# clock_datapath.net
KiCad netlist of a schematic drawn in EAGLE
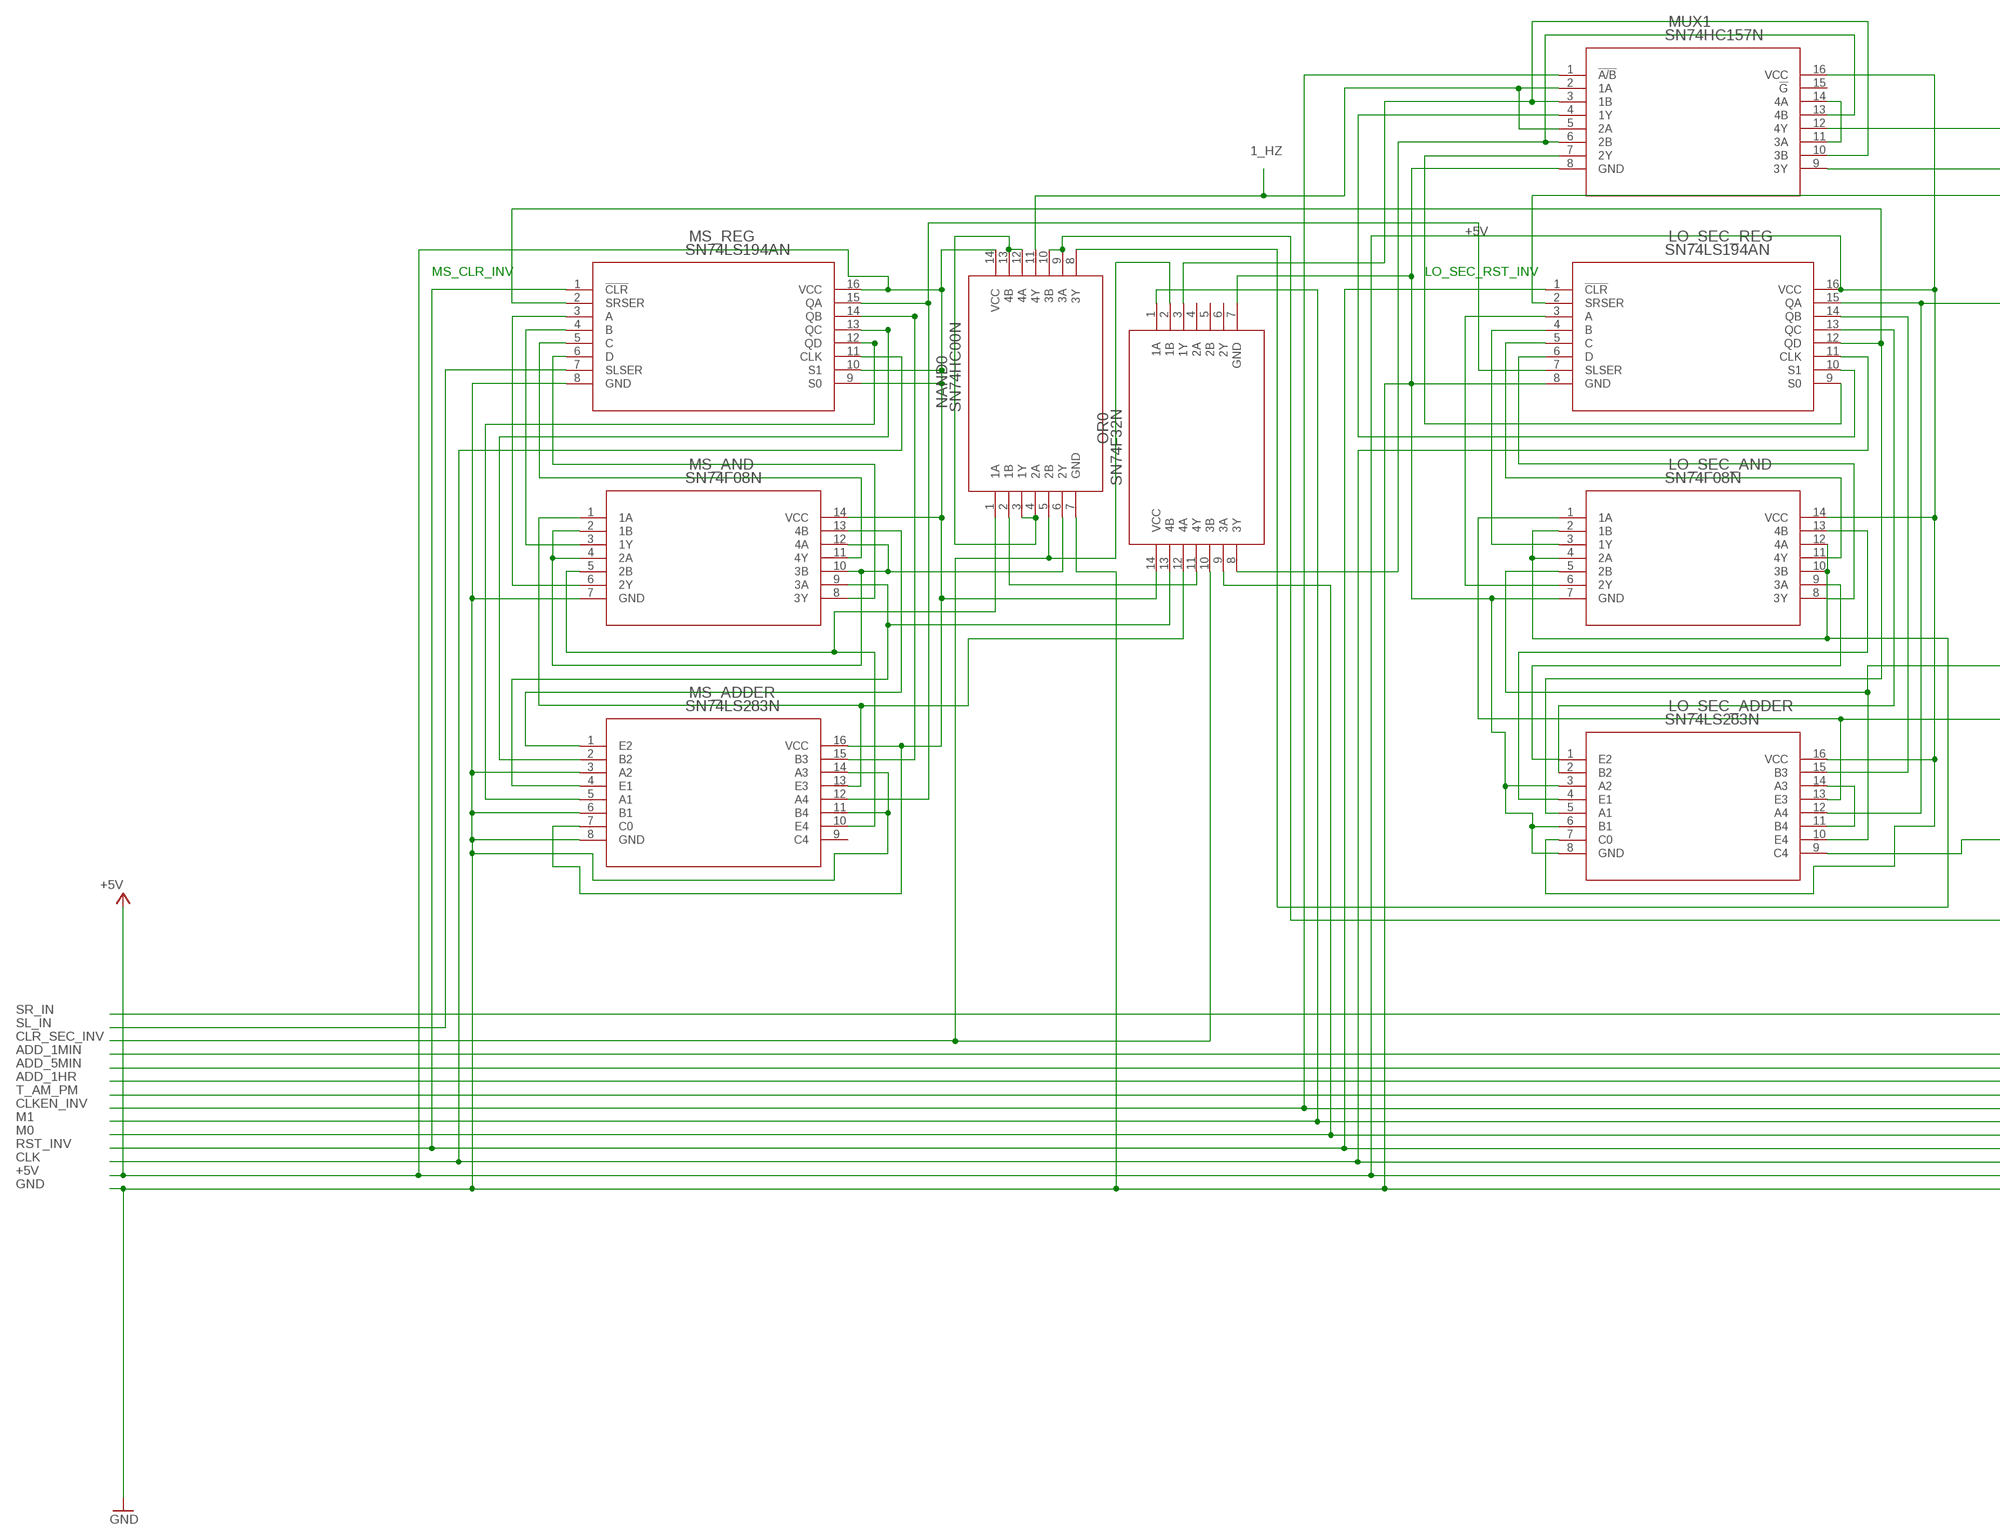
[diagram p0: schematic, sheet 1, part 1 of 3]
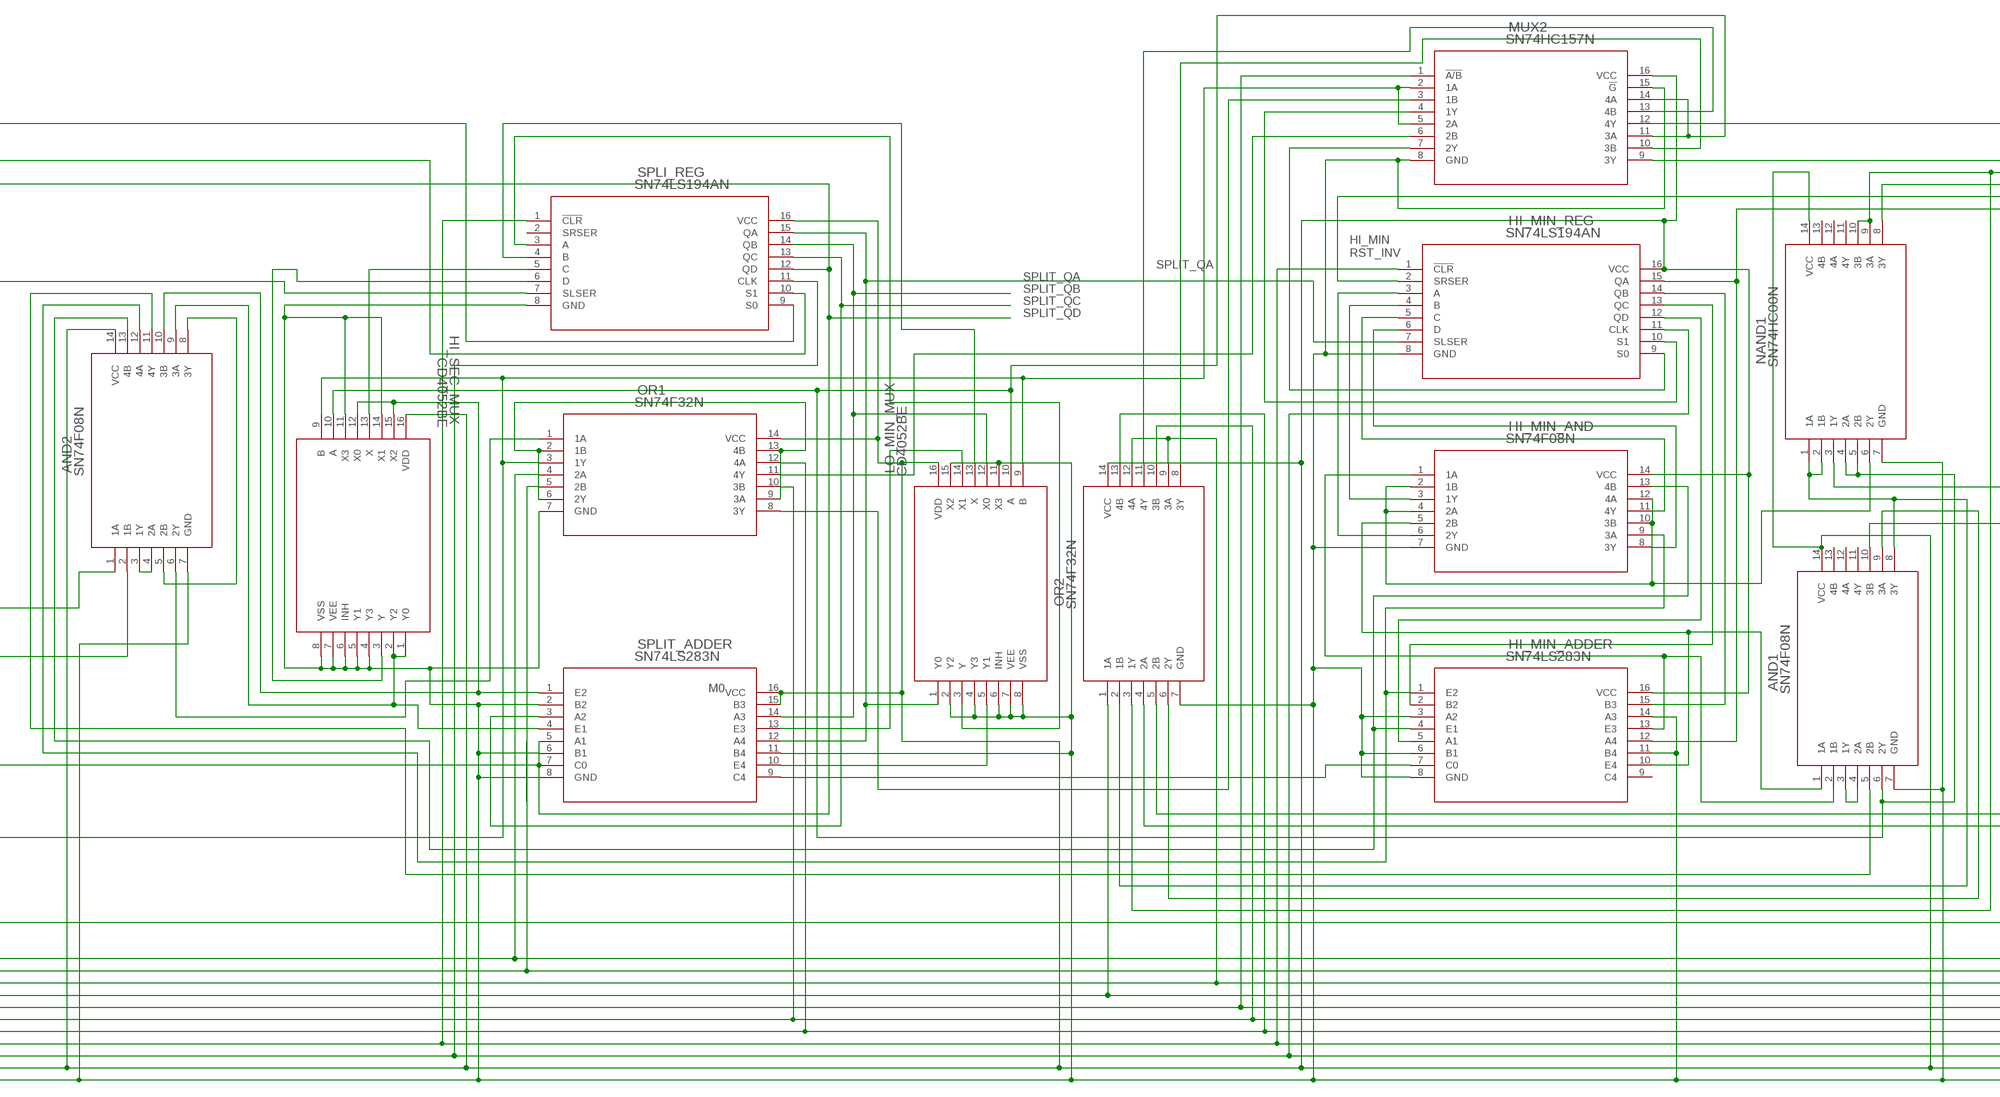
[diagram p1: schematic, sheet 1, part 2 of 3]
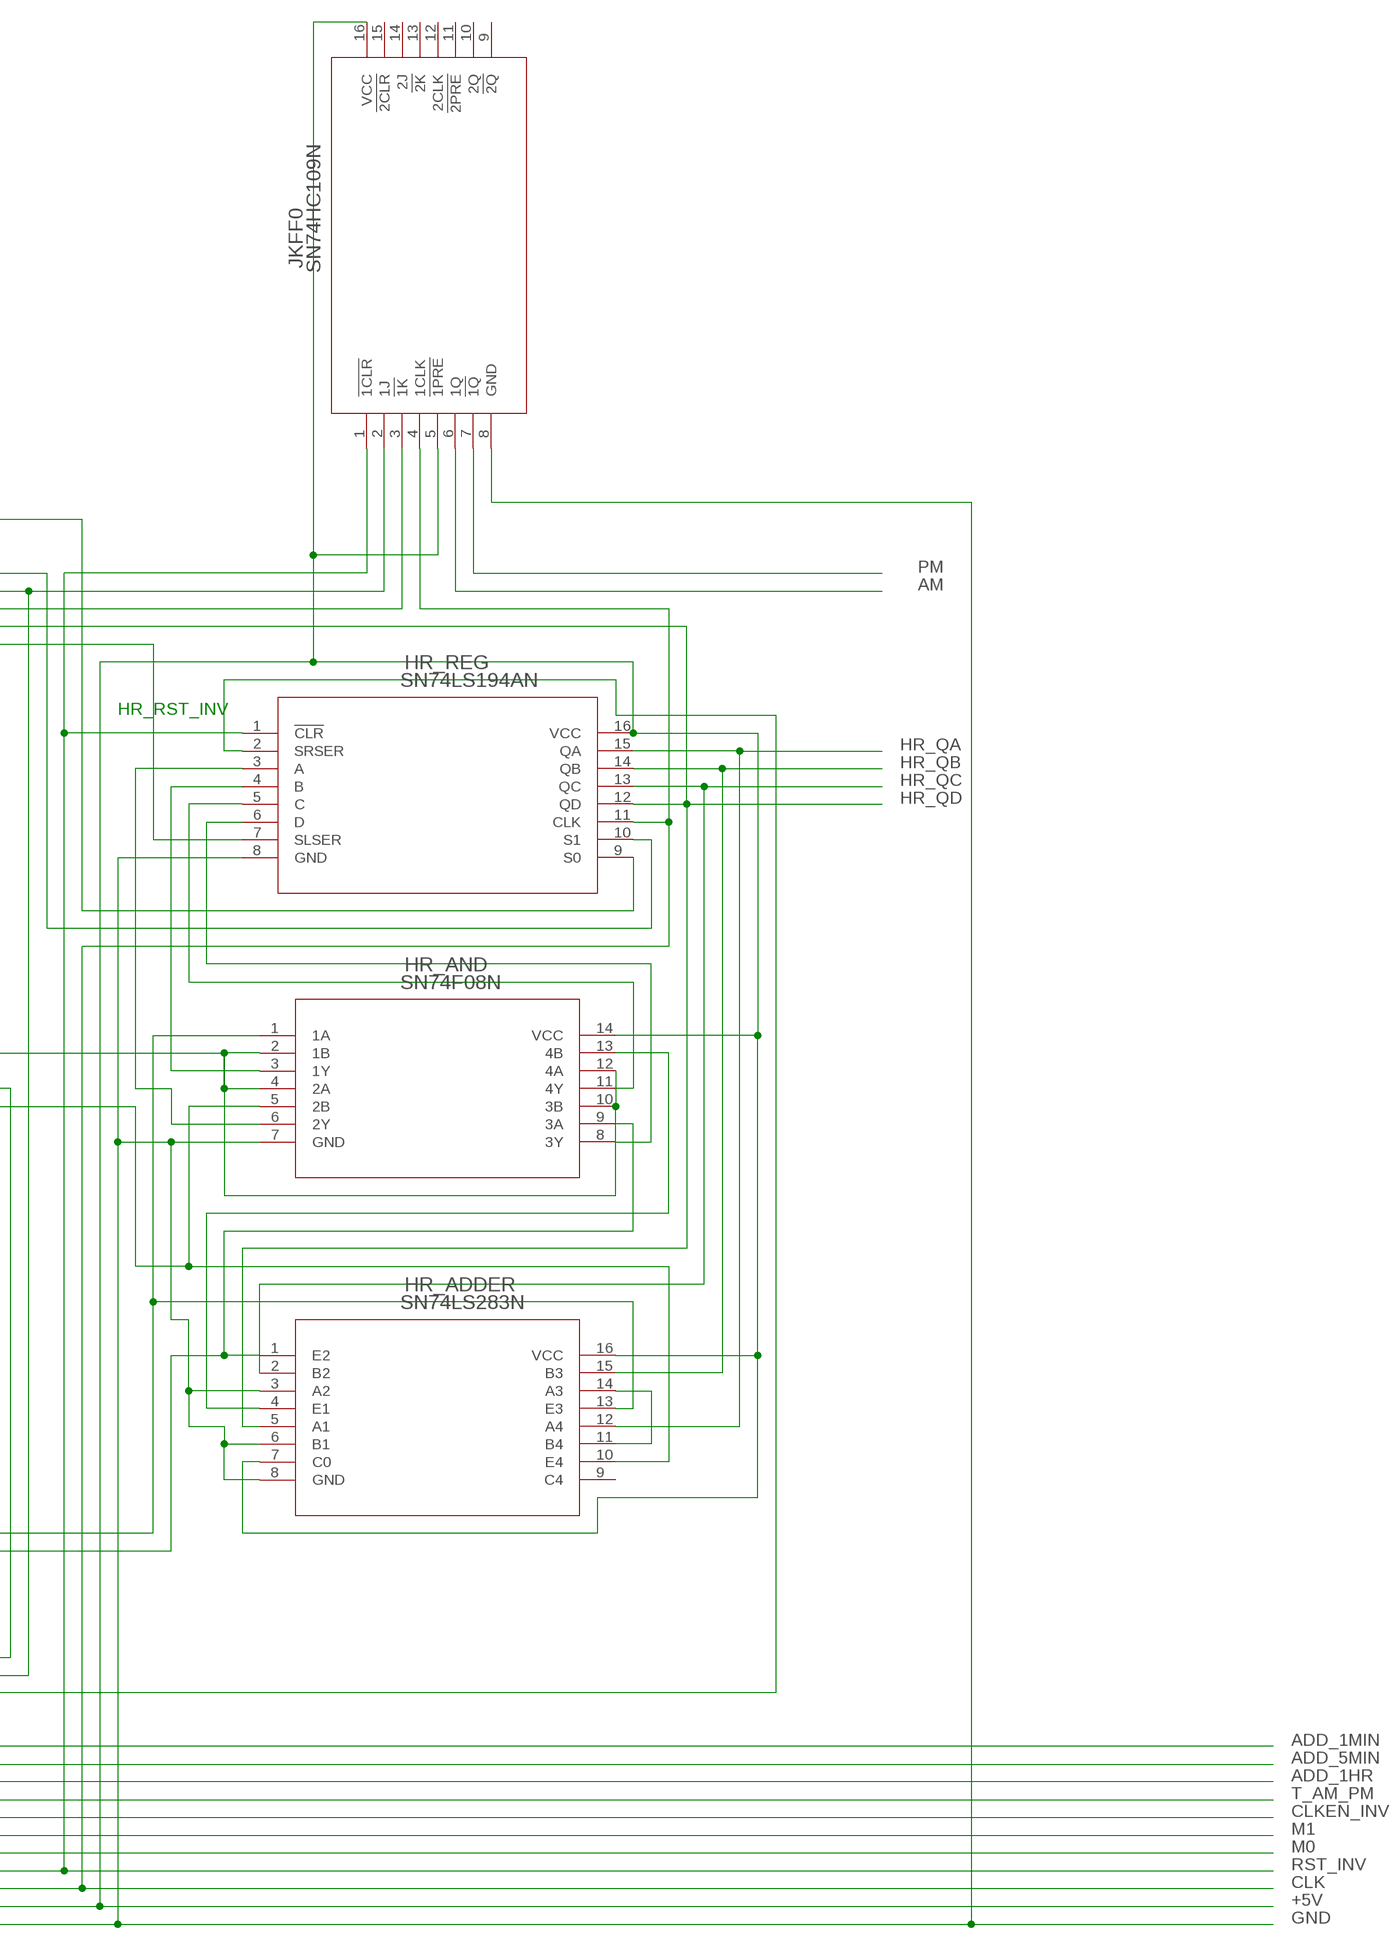
[diagram p2: schematic, sheet 1, part 3 of 3]

(export (version "E")
  (design (tool "Eeschema 10.0.6"))
  (components
    (comp (ref "AND1")
      (value "SN74F08N")
      (footprint "eagle-import:N14")
      (fields
        (field (name "GENERIC_PART_NUMBER") "SN74F08")
        (field (name "MANUFACTURER") "Texas Instruments")
      )
      (libsource (lib "eagle-import") (part "SN74F08N"))
    )
    (comp (ref "AND2")
      (value "SN74F08N")
      (footprint "eagle-import:N14")
      (fields
        (field (name "GENERIC_PART_NUMBER") "SN74F08")
        (field (name "MANUFACTURER") "Texas Instruments")
      )
      (libsource (lib "eagle-import") (part "SN74F08N"))
    )
    (comp (ref "HI_MIN_ADDER")
      (value "SN74LS283N")
      (footprint "eagle-import:N16")
      (fields
        (field (name "GENERIC_PART_NUMBER") "SN74LS283")
        (field (name "MANUFACTURER") "Texas Instruments")
      )
      (libsource (lib "eagle-import") (part "SN74LS283N"))
    )
    (comp (ref "HI_MIN_AND")
      (value "SN74F08N")
      (footprint "eagle-import:N14")
      (fields
        (field (name "GENERIC_PART_NUMBER") "SN74F08")
        (field (name "MANUFACTURER") "Texas Instruments")
      )
      (libsource (lib "eagle-import") (part "SN74F08N"))
    )
    (comp (ref "HI_MIN_REG")
      (value "SN74LS194AN")
      (footprint "eagle-import:N16")
      (fields
        (field (name "GENERIC_PART_NUMBER") "SN74LS194A")
        (field (name "MANUFACTURER") "Texas Instruments")
      )
      (libsource (lib "eagle-import") (part "SN74LS194AN"))
    )
    (comp (ref "HI_SEC_MUX")
      (value "CD4052BE")
      (footprint "eagle-import:N16")
      (fields
        (field (name "GENERIC_PART_NUMBER") "CD4052B")
        (field (name "MANUFACTURER") "Texas Instruments")
      )
      (libsource (lib "eagle-import") (part "CD4052BE"))
    )
    (comp (ref "HR_ADDER")
      (value "SN74LS283N")
      (footprint "eagle-import:N16")
      (fields
        (field (name "GENERIC_PART_NUMBER") "SN74LS283")
        (field (name "MANUFACTURER") "Texas Instruments")
      )
      (libsource (lib "eagle-import") (part "SN74LS283N"))
    )
    (comp (ref "HR_AND")
      (value "SN74F08N")
      (footprint "eagle-import:N14")
      (fields
        (field (name "GENERIC_PART_NUMBER") "SN74F08")
        (field (name "MANUFACTURER") "Texas Instruments")
      )
      (libsource (lib "eagle-import") (part "SN74F08N"))
    )
    (comp (ref "HR_REG")
      (value "SN74LS194AN")
      (footprint "eagle-import:N16")
      (fields
        (field (name "GENERIC_PART_NUMBER") "SN74LS194A")
        (field (name "MANUFACTURER") "Texas Instruments")
      )
      (libsource (lib "eagle-import") (part "SN74LS194AN"))
    )
    (comp (ref "JKFF0")
      (value "SN74HC109N")
      (footprint "eagle-import:N16")
      (fields
        (field (name "GENERIC_PART_NUMBER") "SN74HC109")
        (field (name "MANUFACTURER") "Texas Instruments")
      )
      (libsource (lib "eagle-import") (part "SN74HC109N"))
    )
    (comp (ref "LO_MIN_MUX")
      (value "CD4052BE")
      (footprint "eagle-import:N16")
      (fields
        (field (name "GENERIC_PART_NUMBER") "CD4052B")
        (field (name "MANUFACTURER") "Texas Instruments")
      )
      (libsource (lib "eagle-import") (part "CD4052BE"))
    )
    (comp (ref "LO_SEC_ADDER")
      (value "SN74LS283N")
      (footprint "eagle-import:N16")
      (fields
        (field (name "GENERIC_PART_NUMBER") "SN74LS283")
        (field (name "MANUFACTURER") "Texas Instruments")
      )
      (libsource (lib "eagle-import") (part "SN74LS283N"))
    )
    (comp (ref "LO_SEC_AND")
      (value "SN74F08N")
      (footprint "eagle-import:N14")
      (fields
        (field (name "GENERIC_PART_NUMBER") "SN74F08")
        (field (name "MANUFACTURER") "Texas Instruments")
      )
      (libsource (lib "eagle-import") (part "SN74F08N"))
    )
    (comp (ref "LO_SEC_REG")
      (value "SN74LS194AN")
      (footprint "eagle-import:N16")
      (fields
        (field (name "GENERIC_PART_NUMBER") "SN74LS194A")
        (field (name "MANUFACTURER") "Texas Instruments")
      )
      (libsource (lib "eagle-import") (part "SN74LS194AN"))
    )
    (comp (ref "MS_ADDER")
      (value "SN74LS283N")
      (footprint "eagle-import:N16")
      (fields
        (field (name "GENERIC_PART_NUMBER") "SN74LS283")
        (field (name "MANUFACTURER") "Texas Instruments")
      )
      (libsource (lib "eagle-import") (part "SN74LS283N"))
    )
    (comp (ref "MS_AND")
      (value "SN74F08N")
      (footprint "eagle-import:N14")
      (fields
        (field (name "GENERIC_PART_NUMBER") "SN74F08")
        (field (name "MANUFACTURER") "Texas Instruments")
      )
      (libsource (lib "eagle-import") (part "SN74F08N"))
    )
    (comp (ref "MS_REG")
      (value "SN74LS194AN")
      (footprint "eagle-import:N16")
      (fields
        (field (name "GENERIC_PART_NUMBER") "SN74LS194A")
        (field (name "MANUFACTURER") "Texas Instruments")
      )
      (libsource (lib "eagle-import") (part "SN74LS194AN"))
    )
    (comp (ref "MUX1")
      (value "SN74HC157N")
      (footprint "eagle-import:N16")
      (fields
        (field (name "GENERIC_PART_NUMBER") "SN74HC157")
        (field (name "MANUFACTURER") "Texas Instruments")
      )
      (libsource (lib "eagle-import") (part "SN74HC157N"))
    )
    (comp (ref "MUX2")
      (value "SN74HC157N")
      (footprint "eagle-import:N16")
      (fields
        (field (name "GENERIC_PART_NUMBER") "SN74HC157")
        (field (name "MANUFACTURER") "Texas Instruments")
      )
      (libsource (lib "eagle-import") (part "SN74HC157N"))
    )
    (comp (ref "NAND0")
      (value "SN74HC00N")
      (footprint "eagle-import:N14")
      (fields
        (field (name "GENERIC_PART_NUMBER") "SN74HC00")
        (field (name "MANUFACTURER") "Texas Instruments")
      )
      (libsource (lib "eagle-import") (part "SN74HC00N"))
    )
    (comp (ref "NAND1")
      (value "SN74HC00N")
      (footprint "eagle-import:N14")
      (fields
        (field (name "GENERIC_PART_NUMBER") "SN74HC00")
        (field (name "MANUFACTURER") "Texas Instruments")
      )
      (libsource (lib "eagle-import") (part "SN74HC00N"))
    )
    (comp (ref "OR0")
      (value "SN74F32N")
      (footprint "eagle-import:N14")
      (fields
        (field (name "GENERIC_PART_NUMBER") "SN74F32")
        (field (name "MANUFACTURER") "Texas Instruments")
      )
      (libsource (lib "eagle-import") (part "SN74F32N"))
    )
    (comp (ref "OR1")
      (value "SN74F32N")
      (footprint "eagle-import:N14")
      (fields
        (field (name "GENERIC_PART_NUMBER") "SN74F32")
        (field (name "MANUFACTURER") "Texas Instruments")
      )
      (libsource (lib "eagle-import") (part "SN74F32N"))
    )
    (comp (ref "OR2")
      (value "SN74F32N")
      (footprint "eagle-import:N14")
      (fields
        (field (name "GENERIC_PART_NUMBER") "SN74F32")
        (field (name "MANUFACTURER") "Texas Instruments")
      )
      (libsource (lib "eagle-import") (part "SN74F32N"))
    )
    (comp (ref "SPLIT_ADDER")
      (value "SN74LS283N")
      (footprint "eagle-import:N16")
      (fields
        (field (name "GENERIC_PART_NUMBER") "SN74LS283")
        (field (name "MANUFACTURER") "Texas Instruments")
      )
      (libsource (lib "eagle-import") (part "SN74LS283N"))
    )
    (comp (ref "SPLI_REG")
      (value "SN74LS194AN")
      (footprint "eagle-import:N16")
      (fields
        (field (name "GENERIC_PART_NUMBER") "SN74LS194A")
        (field (name "MANUFACTURER") "Texas Instruments")
      )
      (libsource (lib "eagle-import") (part "SN74LS194AN"))
    )
  )
  (nets
    (net (code "1") (name "+5V") (class "Default")
      (node (ref "AND1") (pin "14") (pinfunction "VCC_14") (pintype "power_in"))
      (node (ref "AND2") (pin "14") (pinfunction "VCC_14") (pintype "power_in"))
      (node (ref "HI_MIN_ADDER") (pin "16") (pinfunction "VCC_16") (pintype "power_in"))
      (node (ref "HI_MIN_AND") (pin "14") (pinfunction "VCC_14") (pintype "power_in"))
      (node (ref "HI_MIN_REG") (pin "16") (pinfunction "VCC_16") (pintype "power_in"))
      (node (ref "HI_SEC_MUX") (pin "16") (pinfunction "VDD_16") (pintype "power_in"))
      (node (ref "HR_ADDER") (pin "16") (pinfunction "VCC_16") (pintype "power_in"))
      (node (ref "HR_ADDER") (pin "7") (pinfunction "C0_7") (pintype "input"))
      (node (ref "HR_AND") (pin "14") (pinfunction "VCC_14") (pintype "power_in"))
      (node (ref "HR_REG") (pin "16") (pinfunction "VCC_16") (pintype "power_in"))
      (node (ref "JKFF0") (pin "16") (pinfunction "VCC_16") (pintype "power_in"))
      (node (ref "JKFF0") (pin "5") (pinfunction "~{1PRE}_5") (pintype "input"))
      (node (ref "LO_MIN_MUX") (pin "16") (pinfunction "VDD_16") (pintype "power_in"))
      (node (ref "LO_SEC_ADDER") (pin "16") (pinfunction "VCC_16") (pintype "power_in"))
      (node (ref "LO_SEC_ADDER") (pin "7") (pinfunction "C0_7") (pintype "input"))
      (node (ref "LO_SEC_AND") (pin "14") (pinfunction "VCC_14") (pintype "power_in"))
      (node (ref "LO_SEC_REG") (pin "16") (pinfunction "VCC_16") (pintype "power_in"))
      (node (ref "MS_ADDER") (pin "16") (pinfunction "VCC_16") (pintype "power_in"))
      (node (ref "MS_ADDER") (pin "7") (pinfunction "C0_7") (pintype "input"))
      (node (ref "MS_AND") (pin "14") (pinfunction "VCC_14") (pintype "power_in"))
      (node (ref "MS_REG") (pin "10") (pinfunction "S1_10") (pintype "input"))
      (node (ref "MS_REG") (pin "16") (pinfunction "VCC_16") (pintype "power_in"))
      (node (ref "MS_REG") (pin "9") (pinfunction "S0_9") (pintype "input"))
      (node (ref "MUX1") (pin "16") (pinfunction "VCC_16") (pintype "power_in"))
      (node (ref "MUX2") (pin "16") (pinfunction "VCC_16") (pintype "power_in"))
      (node (ref "NAND0") (pin "14") (pinfunction "VCC_14") (pintype "power_in"))
      (node (ref "NAND1") (pin "14") (pinfunction "VCC_14") (pintype "power_in"))
      (node (ref "OR0") (pin "14") (pinfunction "VCC_14") (pintype "power_in"))
      (node (ref "OR1") (pin "14") (pinfunction "VCC_14") (pintype "power_in"))
      (node (ref "OR2") (pin "14") (pinfunction "VCC_14") (pintype "power_in"))
      (node (ref "SPLIT_ADDER") (pin "15") (pinfunction "B3_15") (pintype "input"))
      (node (ref "SPLIT_ADDER") (pin "16") (pinfunction "VCC_16") (pintype "power_in"))
      (node (ref "SPLI_REG") (pin "16") (pinfunction "VCC_16") (pintype "power_in"))
    )
    (net (code "2") (name "/1_HZ") (class "Default")
      (node (ref "MUX1") (pin "2") (pinfunction "1A_2") (pintype "input"))
      (node (ref "MUX1") (pin "5") (pinfunction "2A_5") (pintype "input"))
      (node (ref "NAND0") (pin "11") (pinfunction "4Y_11") (pintype "output"))
    )
    (net (code "3") (name "/ADD_1HR") (class "Default")
      (node (ref "OR2") (pin "12") (pinfunction "4A_12") (pintype "input"))
      (node (ref "OR2") (pin "9") (pinfunction "3A_9") (pintype "input"))
    )
    (net (code "4") (name "/ADD_1MIN") (class "Default")
      (node (ref "OR1") (pin "4") (pinfunction "2A_4") (pintype "input"))
    )
    (net (code "5") (name "/ADD_5MIN") (class "Default")
      (node (ref "OR1") (pin "5") (pinfunction "2B_5") (pintype "input"))
    )
    (net (code "6") (name "/AM") (class "Default")
      (node (ref "JKFF0") (pin "6") (pinfunction "1Q_6") (pintype "output"))
    )
    (net (code "7") (name "/CLK") (class "Default")
      (node (ref "HI_MIN_REG") (pin "11") (pinfunction "CLK_11") (pintype "input"))
      (node (ref "HR_REG") (pin "11") (pinfunction "CLK_11") (pintype "input"))
      (node (ref "JKFF0") (pin "4") (pinfunction "1CLK_4") (pintype "input"))
      (node (ref "LO_SEC_REG") (pin "11") (pinfunction "CLK_11") (pintype "input"))
      (node (ref "MS_REG") (pin "11") (pinfunction "CLK_11") (pintype "input"))
      (node (ref "SPLI_REG") (pin "11") (pinfunction "CLK_11") (pintype "input"))
    )
    (net (code "8") (name "/CLKEN_INV") (class "Default")
      (node (ref "MUX1") (pin "1") (pinfunction "~{A/B}_1") (pintype "input"))
      (node (ref "MUX2") (pin "1") (pinfunction "~{A/B}_1") (pintype "input"))
    )
    (net (code "9") (name "/CLR_SEC_INV") (class "Default")
      (node (ref "NAND0") (pin "5") (pinfunction "2B_5") (pintype "input"))
      (node (ref "OR0") (pin "10") (pinfunction "3B_10") (pintype "input"))
      (node (ref "OR0") (pin "2") (pinfunction "1B_2") (pintype "input"))
    )
    (net (code "10") (name "/HR_QA") (class "Default")
      (node (ref "HR_ADDER") (pin "12") (pinfunction "A4_12") (pintype "input"))
      (node (ref "HR_REG") (pin "15") (pinfunction "QA_15") (pintype "output"))
    )
    (net (code "11") (name "/HR_QB") (class "Default")
      (node (ref "HR_ADDER") (pin "15") (pinfunction "B3_15") (pintype "input"))
      (node (ref "HR_REG") (pin "14") (pinfunction "QB_14") (pintype "output"))
    )
    (net (code "12") (name "/HR_QC") (class "Default")
      (node (ref "HR_ADDER") (pin "2") (pinfunction "B2_2") (pintype "input"))
      (node (ref "HR_REG") (pin "13") (pinfunction "QC_13") (pintype "output"))
    )
    (net (code "13") (name "/HR_QD") (class "Default")
      (node (ref "HI_MIN_REG") (pin "2") (pinfunction "SRSER_2") (pintype "input"))
      (node (ref "HR_ADDER") (pin "5") (pinfunction "A1_5") (pintype "input"))
      (node (ref "HR_REG") (pin "12") (pinfunction "QD_12") (pintype "output"))
    )
    (net (code "14") (name "/M0") (class "Default")
      (node (ref "OR0") (pin "9") (pinfunction "3A_9") (pintype "input"))
      (node (ref "OR1") (pin "12") (pinfunction "4A_12") (pintype "input"))
      (node (ref "OR2") (pin "13") (pinfunction "4B_13") (pintype "input"))
    )
    (net (code "15") (name "/M1") (class "Default")
      (node (ref "OR0") (pin "1") (pinfunction "1A_1") (pintype "input"))
      (node (ref "OR1") (pin "10") (pinfunction "3B_10") (pintype "input"))
      (node (ref "OR2") (pin "10") (pinfunction "3B_10") (pintype "input"))
    )
    (net (code "16") (name "/PM") (class "Default")
      (node (ref "JKFF0") (pin "7") (pinfunction "~{1Q}_7") (pintype "output"))
    )
    (net (code "17") (name "/RST_INV") (class "Default")
      (node (ref "HI_MIN_REG") (pin "1") (pinfunction "~{CLR}_1") (pintype "input"))
      (node (ref "HR_REG") (pin "1") (pinfunction "~{CLR}_1") (pintype "input"))
      (node (ref "JKFF0") (pin "1") (pinfunction "~{1CLR}_1") (pintype "input"))
      (node (ref "LO_SEC_REG") (pin "1") (pinfunction "~{CLR}_1") (pintype "input"))
      (node (ref "MS_REG") (pin "1") (pinfunction "~{CLR}_1") (pintype "input"))
      (node (ref "SPLI_REG") (pin "1") (pinfunction "~{CLR}_1") (pintype "input"))
    )
    (net (code "18") (name "/SL_IN") (class "Default")
      (node (ref "MS_REG") (pin "7") (pinfunction "SLSER_7") (pintype "input"))
    )
    (net (code "19") (name "/SPLIT_QA") (class "Default")
      (node (ref "HI_MIN_REG") (pin "7") (pinfunction "SLSER_7") (pintype "input"))
      (node (ref "LO_MIN_MUX") (pin "1") (pinfunction "Y0_1") (pintype "bidirectional"))
      (node (ref "SPLIT_ADDER") (pin "12") (pinfunction "A4_12") (pintype "input"))
      (node (ref "SPLI_REG") (pin "15") (pinfunction "QA_15") (pintype "output"))
    )
    (net (code "20") (name "/SPLIT_QB") (class "Default")
      (node (ref "LO_MIN_MUX") (pin "12") (pinfunction "X0_12") (pintype "bidirectional"))
      (node (ref "SPLIT_ADDER") (pin "14") (pinfunction "A3_14") (pintype "input"))
      (node (ref "SPLI_REG") (pin "14") (pinfunction "QB_14") (pintype "output"))
    )
    (net (code "21") (name "/SPLIT_QC") (class "Default")
      (node (ref "SPLIT_ADDER") (pin "3") (pinfunction "A2_3") (pintype "input"))
      (node (ref "SPLI_REG") (pin "13") (pinfunction "QC_13") (pintype "output"))
    )
    (net (code "22") (name "/SPLIT_QD") (class "Default")
      (node (ref "LO_SEC_ADDER") (pin "9") (pinfunction "C4_9") (pintype "input"))
      (node (ref "LO_SEC_REG") (pin "2") (pinfunction "SRSER_2") (pintype "input"))
      (node (ref "SPLIT_ADDER") (pin "5") (pinfunction "A1_5") (pintype "input"))
      (node (ref "SPLIT_ADDER") (pin "7") (pinfunction "C0_7") (pintype "input"))
      (node (ref "SPLI_REG") (pin "12") (pinfunction "QD_12") (pintype "output"))
    )
    (net (code "23") (name "/SR_IN") (class "Default")
      (node (ref "HR_REG") (pin "2") (pinfunction "SRSER_2") (pintype "input"))
    )
    (net (code "24") (name "/T_AM_PM") (class "Default")
      (node (ref "OR2") (pin "1") (pinfunction "1A_1") (pintype "input"))
    )
    (net (code "25") (name "GND") (class "Default")
      (node (ref "AND1") (pin "7") (pinfunction "GND_7") (pintype "power_in"))
      (node (ref "AND2") (pin "7") (pinfunction "GND_7") (pintype "power_in"))
      (node (ref "HI_MIN_ADDER") (pin "11") (pinfunction "B4_11") (pintype "input"))
      (node (ref "HI_MIN_ADDER") (pin "14") (pinfunction "A3_14") (pintype "input"))
      (node (ref "HI_MIN_ADDER") (pin "3") (pinfunction "A2_3") (pintype "input"))
      (node (ref "HI_MIN_ADDER") (pin "6") (pinfunction "B1_6") (pintype "input"))
      (node (ref "HI_MIN_ADDER") (pin "8") (pinfunction "GND_8") (pintype "power_in"))
      (node (ref "HI_MIN_AND") (pin "7") (pinfunction "GND_7") (pintype "power_in"))
      (node (ref "HI_MIN_REG") (pin "8") (pinfunction "GND_8") (pintype "power_in"))
      (node (ref "HI_SEC_MUX") (pin "11") (pinfunction "X3_11") (pintype "bidirectional"))
      (node (ref "HI_SEC_MUX") (pin "14") (pinfunction "X1_14") (pintype "bidirectional"))
      (node (ref "HI_SEC_MUX") (pin "4") (pinfunction "Y3_4") (pintype "bidirectional"))
      (node (ref "HI_SEC_MUX") (pin "5") (pinfunction "Y1_5") (pintype "bidirectional"))
      (node (ref "HI_SEC_MUX") (pin "6") (pinfunction "INH_6") (pintype "passive"))
      (node (ref "HI_SEC_MUX") (pin "7") (pinfunction "VEE_7") (pintype "power_in"))
      (node (ref "HI_SEC_MUX") (pin "8") (pinfunction "VSS_8") (pintype "power_in"))
      (node (ref "HR_ADDER") (pin "3") (pinfunction "A2_3") (pintype "input"))
      (node (ref "HR_ADDER") (pin "6") (pinfunction "B1_6") (pintype "input"))
      (node (ref "HR_ADDER") (pin "8") (pinfunction "GND_8") (pintype "power_in"))
      (node (ref "HR_AND") (pin "7") (pinfunction "GND_7") (pintype "power_in"))
      (node (ref "HR_REG") (pin "8") (pinfunction "GND_8") (pintype "power_in"))
      (node (ref "JKFF0") (pin "8") (pinfunction "GND_8") (pintype "power_in"))
      (node (ref "LO_MIN_MUX") (pin "11") (pinfunction "X3_11") (pintype "bidirectional"))
      (node (ref "LO_MIN_MUX") (pin "15") (pinfunction "X2_15") (pintype "bidirectional"))
      (node (ref "LO_MIN_MUX") (pin "2") (pinfunction "Y2_2") (pintype "bidirectional"))
      (node (ref "LO_MIN_MUX") (pin "4") (pinfunction "Y3_4") (pintype "bidirectional"))
      (node (ref "LO_MIN_MUX") (pin "6") (pinfunction "INH_6") (pintype "passive"))
      (node (ref "LO_MIN_MUX") (pin "7") (pinfunction "VEE_7") (pintype "power_in"))
      (node (ref "LO_MIN_MUX") (pin "8") (pinfunction "VSS_8") (pintype "power_in"))
      (node (ref "LO_SEC_ADDER") (pin "3") (pinfunction "A2_3") (pintype "input"))
      (node (ref "LO_SEC_ADDER") (pin "6") (pinfunction "B1_6") (pintype "input"))
      (node (ref "LO_SEC_ADDER") (pin "8") (pinfunction "GND_8") (pintype "power_in"))
      (node (ref "LO_SEC_AND") (pin "7") (pinfunction "GND_7") (pintype "power_in"))
      (node (ref "LO_SEC_REG") (pin "8") (pinfunction "GND_8") (pintype "power_in"))
      (node (ref "MS_ADDER") (pin "11") (pinfunction "B4_11") (pintype "input"))
      (node (ref "MS_ADDER") (pin "14") (pinfunction "A3_14") (pintype "input"))
      (node (ref "MS_ADDER") (pin "3") (pinfunction "A2_3") (pintype "input"))
      (node (ref "MS_ADDER") (pin "6") (pinfunction "B1_6") (pintype "input"))
      (node (ref "MS_ADDER") (pin "8") (pinfunction "GND_8") (pintype "power_in"))
      (node (ref "MS_AND") (pin "7") (pinfunction "GND_7") (pintype "power_in"))
      (node (ref "MS_REG") (pin "8") (pinfunction "GND_8") (pintype "power_in"))
      (node (ref "MUX1") (pin "8") (pinfunction "GND_8") (pintype "power_in"))
      (node (ref "MUX2") (pin "15") (pinfunction "~{G}_15") (pintype "input"))
      (node (ref "MUX2") (pin "8") (pinfunction "GND_8") (pintype "power_in"))
      (node (ref "NAND0") (pin "7") (pinfunction "GND_7") (pintype "power_in"))
      (node (ref "NAND1") (pin "7") (pinfunction "GND_7") (pintype "power_in"))
      (node (ref "OR0") (pin "7") (pinfunction "GND_7") (pintype "power_in"))
      (node (ref "OR1") (pin "7") (pinfunction "GND_7") (pintype "power_in"))
      (node (ref "OR2") (pin "7") (pinfunction "GND_7") (pintype "power_in"))
      (node (ref "SPLIT_ADDER") (pin "11") (pinfunction "B4_11") (pintype "input"))
      (node (ref "SPLIT_ADDER") (pin "2") (pinfunction "B2_2") (pintype "input"))
      (node (ref "SPLIT_ADDER") (pin "6") (pinfunction "B1_6") (pintype "input"))
      (node (ref "SPLIT_ADDER") (pin "8") (pinfunction "GND_8") (pintype "power_in"))
      (node (ref "SPLI_REG") (pin "8") (pinfunction "GND_8") (pintype "power_in"))
    )
    (net (code "26") (name "Net-(AND1-1A)") (class "Default")
      (node (ref "AND1") (pin "1") (pinfunction "1A_1") (pintype "input"))
      (node (ref "HI_MIN_ADDER") (pin "10") (pinfunction "E4_10") (pintype "output"))
      (node (ref "HI_MIN_AND") (pin "5") (pinfunction "2B_5") (pintype "input"))
    )
    (net (code "27") (name "Net-(AND1-1B)") (class "Default")
      (node (ref "AND1") (pin "2") (pinfunction "1B_2") (pintype "input"))
      (node (ref "HI_MIN_ADDER") (pin "13") (pinfunction "E3_13") (pintype "output"))
      (node (ref "HI_MIN_AND") (pin "1") (pinfunction "1A_1") (pintype "input"))
    )
    (net (code "28") (name "Net-(AND1-1Y)") (class "Default")
      (node (ref "AND1") (pin "3") (pinfunction "1Y_3") (pintype "output"))
      (node (ref "AND1") (pin "4") (pinfunction "2A_4") (pintype "input"))
    )
    (net (code "29") (name "Net-(AND1-2B)") (class "Default")
      (node (ref "AND1") (pin "5") (pinfunction "2B_5") (pintype "input"))
      (node (ref "AND2") (pin "11") (pinfunction "4Y_11") (pintype "output"))
    )
    (net (code "30") (name "Net-(AND1-2Y)") (class "Default")
      (node (ref "AND1") (pin "6") (pinfunction "2Y_6") (pintype "output"))
      (node (ref "HI_SEC_MUX") (pin "10") (pinfunction "A_10") (pintype "passive"))
      (node (ref "LO_MIN_MUX") (pin "10") (pinfunction "A_10") (pintype "passive"))
      (node (ref "MUX2") (pin "11") (pinfunction "3A_11") (pintype "input"))
      (node (ref "MUX2") (pin "14") (pinfunction "4A_14") (pintype "input"))
      (node (ref "NAND1") (pin "4") (pinfunction "2A_4") (pintype "input"))
      (node (ref "NAND1") (pin "5") (pinfunction "2B_5") (pintype "input"))
    )
    (net (code "31") (name "Net-(AND1-3A)") (class "Default")
      (node (ref "AND1") (pin "9") (pinfunction "3A_9") (pintype "input"))
      (node (ref "OR2") (pin "6") (pinfunction "2Y_6") (pintype "output"))
    )
    (net (code "32") (name "Net-(AND1-3B)") (class "Default")
      (node (ref "AND1") (pin "10") (pinfunction "3B_10") (pintype "input"))
      (node (ref "HR_ADDER") (pin "10") (pinfunction "E4_10") (pintype "output"))
      (node (ref "HR_AND") (pin "5") (pinfunction "2B_5") (pintype "input"))
    )
    (net (code "33") (name "Net-(AND1-3Y)") (class "Default")
      (node (ref "AND1") (pin "8") (pinfunction "3Y_8") (pintype "output"))
      (node (ref "NAND1") (pin "1") (pinfunction "1A_1") (pintype "input"))
      (node (ref "NAND1") (pin "2") (pinfunction "1B_2") (pintype "input"))
      (node (ref "OR2") (pin "2") (pinfunction "1B_2") (pintype "input"))
    )
    (net (code "34") (name "Net-(AND2-1A)") (class "Default")
      (node (ref "AND2") (pin "1") (pinfunction "1A_1") (pintype "input"))
      (node (ref "LO_SEC_ADDER") (pin "10") (pinfunction "E4_10") (pintype "output"))
      (node (ref "LO_SEC_AND") (pin "5") (pinfunction "2B_5") (pintype "input"))
    )
    (net (code "35") (name "Net-(AND2-1B)") (class "Default")
      (node (ref "AND2") (pin "2") (pinfunction "1B_2") (pintype "input"))
      (node (ref "LO_SEC_ADDER") (pin "13") (pinfunction "E3_13") (pintype "output"))
      (node (ref "LO_SEC_AND") (pin "1") (pinfunction "1A_1") (pintype "input"))
    )
    (net (code "36") (name "Net-(AND2-1Y)") (class "Default")
      (node (ref "AND2") (pin "3") (pinfunction "1Y_3") (pintype "output"))
      (node (ref "AND2") (pin "4") (pinfunction "2A_4") (pintype "input"))
    )
    (net (code "37") (name "Net-(AND2-2B)") (class "Default")
      (node (ref "AND2") (pin "5") (pinfunction "2B_5") (pintype "input"))
      (node (ref "AND2") (pin "8") (pinfunction "3Y_8") (pintype "output"))
    )
    (net (code "38") (name "Net-(AND2-2Y)") (class "Default")
      (node (ref "AND2") (pin "6") (pinfunction "2Y_6") (pintype "output"))
      (node (ref "OR1") (pin "1") (pinfunction "1A_1") (pintype "input"))
    )
    (net (code "39") (name "Net-(AND2-3A)") (class "Default")
      (node (ref "AND2") (pin "9") (pinfunction "3A_9") (pintype "input"))
      (node (ref "HI_SEC_MUX") (pin "1") (pinfunction "Y0_1") (pintype "bidirectional"))
      (node (ref "HI_SEC_MUX") (pin "2") (pinfunction "Y2_2") (pintype "bidirectional"))
      (node (ref "SPLIT_ADDER") (pin "4") (pinfunction "E1_4") (pintype "output"))
    )
    (net (code "40") (name "Net-(AND2-3B)") (class "Default")
      (node (ref "AND2") (pin "10") (pinfunction "3B_10") (pintype "input"))
      (node (ref "HI_SEC_MUX") (pin "12") (pinfunction "X0_12") (pintype "bidirectional"))
      (node (ref "HI_SEC_MUX") (pin "15") (pinfunction "X2_15") (pintype "bidirectional"))
      (node (ref "SPLIT_ADDER") (pin "1") (pinfunction "E2_1") (pintype "output"))
    )
    (net (code "41") (name "Net-(AND2-4A)") (class "Default")
      (node (ref "AND2") (pin "12") (pinfunction "4A_12") (pintype "input"))
      (node (ref "HI_MIN_ADDER") (pin "1") (pinfunction "E2_1") (pintype "output"))
      (node (ref "HI_MIN_AND") (pin "9") (pinfunction "3A_9") (pintype "input"))
    )
    (net (code "42") (name "Net-(AND2-4B)") (class "Default")
      (node (ref "AND2") (pin "13") (pinfunction "4B_13") (pintype "input"))
      (node (ref "HI_MIN_ADDER") (pin "4") (pinfunction "E1_4") (pintype "output"))
      (node (ref "HI_MIN_AND") (pin "13") (pinfunction "4B_13") (pintype "input"))
    )
    (net (code "43") (name "Net-(HI_MIN_ADDER-A1)") (class "Default")
      (node (ref "HI_MIN_ADDER") (pin "5") (pinfunction "A1_5") (pintype "input"))
      (node (ref "HI_MIN_REG") (pin "12") (pinfunction "QD_12") (pintype "output"))
    )
    (net (code "44") (name "Net-(HI_MIN_ADDER-A4)") (class "Default")
      (node (ref "HI_MIN_ADDER") (pin "12") (pinfunction "A4_12") (pintype "input"))
      (node (ref "HI_MIN_REG") (pin "15") (pinfunction "QA_15") (pintype "output"))
      (node (ref "HR_REG") (pin "7") (pinfunction "SLSER_7") (pintype "input"))
    )
    (net (code "45") (name "Net-(HI_MIN_ADDER-B2)") (class "Default")
      (node (ref "HI_MIN_ADDER") (pin "2") (pinfunction "B2_2") (pintype "input"))
      (node (ref "HI_MIN_REG") (pin "13") (pinfunction "QC_13") (pintype "output"))
    )
    (net (code "46") (name "Net-(HI_MIN_ADDER-B3)") (class "Default")
      (node (ref "HI_MIN_ADDER") (pin "15") (pinfunction "B3_15") (pintype "input"))
      (node (ref "HI_MIN_REG") (pin "14") (pinfunction "QB_14") (pintype "output"))
    )
    (net (code "47") (name "Net-(HI_MIN_ADDER-C0)") (class "Default")
      (node (ref "HI_MIN_ADDER") (pin "7") (pinfunction "C0_7") (pintype "input"))
      (node (ref "SPLIT_ADDER") (pin "9") (pinfunction "C4_9") (pintype "input"))
    )
    (net (code "48") (name "Net-(HI_MIN_AND-1B)") (class "Default")
      (node (ref "HI_MIN_AND") (pin "10") (pinfunction "3B_10") (pintype "input"))
      (node (ref "HI_MIN_AND") (pin "12") (pinfunction "4A_12") (pintype "input"))
      (node (ref "HI_MIN_AND") (pin "2") (pinfunction "1B_2") (pintype "input"))
      (node (ref "HI_MIN_AND") (pin "4") (pinfunction "2A_4") (pintype "input"))
      (node (ref "NAND1") (pin "6") (pinfunction "2Y_6") (pintype "output"))
    )
    (net (code "49") (name "Net-(HI_MIN_AND-1Y)") (class "Default")
      (node (ref "HI_MIN_AND") (pin "3") (pinfunction "1Y_3") (pintype "output"))
      (node (ref "HI_MIN_REG") (pin "4") (pinfunction "B_4") (pintype "input"))
    )
    (net (code "50") (name "Net-(HI_MIN_AND-2Y)") (class "Default")
      (node (ref "HI_MIN_AND") (pin "6") (pinfunction "2Y_6") (pintype "output"))
      (node (ref "HI_MIN_REG") (pin "3") (pinfunction "A_3") (pintype "input"))
    )
    (net (code "51") (name "Net-(HI_MIN_AND-3Y)") (class "Default")
      (node (ref "HI_MIN_AND") (pin "8") (pinfunction "3Y_8") (pintype "output"))
      (node (ref "HI_MIN_REG") (pin "6") (pinfunction "D_6") (pintype "input"))
    )
    (net (code "52") (name "Net-(HI_MIN_AND-4Y)") (class "Default")
      (node (ref "HI_MIN_AND") (pin "11") (pinfunction "4Y_11") (pintype "output"))
      (node (ref "HI_MIN_REG") (pin "5") (pinfunction "C_5") (pintype "input"))
    )
    (net (code "53") (name "Net-(HI_MIN_REG-S0)") (class "Default")
      (node (ref "HI_MIN_REG") (pin "9") (pinfunction "S0_9") (pintype "input"))
      (node (ref "MUX2") (pin "7") (pinfunction "2Y_7") (pintype "output"))
    )
    (net (code "54") (name "Net-(HI_MIN_REG-S1)") (class "Default")
      (node (ref "HI_MIN_REG") (pin "10") (pinfunction "S1_10") (pintype "input"))
      (node (ref "MUX2") (pin "4") (pinfunction "1Y_4") (pintype "output"))
    )
    (net (code "55") (name "Net-(HI_SEC_MUX-B)") (class "Default")
      (node (ref "HI_SEC_MUX") (pin "9") (pinfunction "B_9") (pintype "passive"))
      (node (ref "LO_MIN_MUX") (pin "9") (pinfunction "B_9") (pintype "passive"))
      (node (ref "MUX2") (pin "2") (pinfunction "1A_2") (pintype "input"))
      (node (ref "MUX2") (pin "5") (pinfunction "2A_5") (pintype "input"))
      (node (ref "NAND0") (pin "10") (pinfunction "3B_10") (pintype "input"))
      (node (ref "NAND0") (pin "9") (pinfunction "3A_9") (pintype "input"))
      (node (ref "OR1") (pin "3") (pinfunction "1Y_3") (pintype "output"))
    )
    (net (code "56") (name "Net-(HI_SEC_MUX-X)") (class "Default")
      (node (ref "HI_SEC_MUX") (pin "13") (pinfunction "X_13") (pintype "bidirectional"))
      (node (ref "SPLI_REG") (pin "5") (pinfunction "C_5") (pintype "input"))
    )
    (net (code "57") (name "Net-(HI_SEC_MUX-Y)") (class "Default")
      (node (ref "HI_SEC_MUX") (pin "3") (pinfunction "Y_3") (pintype "bidirectional"))
      (node (ref "SPLI_REG") (pin "6") (pinfunction "D_6") (pintype "input"))
    )
    (net (code "58") (name "Net-(HR_ADDER-A3)") (class "Default")
      (node (ref "HR_ADDER") (pin "11") (pinfunction "B4_11") (pintype "input"))
      (node (ref "HR_ADDER") (pin "14") (pinfunction "A3_14") (pintype "input"))
    )
    (net (code "59") (name "Net-(HR_ADDER-E1)") (class "Default")
      (node (ref "HR_ADDER") (pin "4") (pinfunction "E1_4") (pintype "output"))
      (node (ref "HR_AND") (pin "13") (pinfunction "4B_13") (pintype "input"))
    )
    (net (code "60") (name "Net-(HR_ADDER-E2)") (class "Default")
      (node (ref "HR_ADDER") (pin "1") (pinfunction "E2_1") (pintype "output"))
      (node (ref "HR_AND") (pin "9") (pinfunction "3A_9") (pintype "input"))
      (node (ref "OR2") (pin "4") (pinfunction "2A_4") (pintype "input"))
    )
    (net (code "61") (name "Net-(HR_ADDER-E3)") (class "Default")
      (node (ref "HR_ADDER") (pin "13") (pinfunction "E3_13") (pintype "output"))
      (node (ref "HR_AND") (pin "1") (pinfunction "1A_1") (pintype "input"))
      (node (ref "OR2") (pin "5") (pinfunction "2B_5") (pintype "input"))
    )
    (net (code "62") (name "Net-(HR_AND-1B)") (class "Default")
      (node (ref "HR_AND") (pin "10") (pinfunction "3B_10") (pintype "input"))
      (node (ref "HR_AND") (pin "12") (pinfunction "4A_12") (pintype "input"))
      (node (ref "HR_AND") (pin "2") (pinfunction "1B_2") (pintype "input"))
      (node (ref "HR_AND") (pin "4") (pinfunction "2A_4") (pintype "input"))
      (node (ref "NAND1") (pin "3") (pinfunction "1Y_3") (pintype "output"))
    )
    (net (code "63") (name "Net-(HR_AND-1Y)") (class "Default")
      (node (ref "HR_AND") (pin "3") (pinfunction "1Y_3") (pintype "output"))
      (node (ref "HR_REG") (pin "4") (pinfunction "B_4") (pintype "input"))
    )
    (net (code "64") (name "Net-(HR_AND-2Y)") (class "Default")
      (node (ref "HR_AND") (pin "6") (pinfunction "2Y_6") (pintype "output"))
      (node (ref "HR_REG") (pin "3") (pinfunction "A_3") (pintype "input"))
    )
    (net (code "65") (name "Net-(HR_AND-3Y)") (class "Default")
      (node (ref "HR_AND") (pin "8") (pinfunction "3Y_8") (pintype "output"))
      (node (ref "HR_REG") (pin "6") (pinfunction "D_6") (pintype "input"))
    )
    (net (code "66") (name "Net-(HR_AND-4Y)") (class "Default")
      (node (ref "HR_AND") (pin "11") (pinfunction "4Y_11") (pintype "output"))
      (node (ref "HR_REG") (pin "5") (pinfunction "C_5") (pintype "input"))
    )
    (net (code "67") (name "Net-(HR_REG-S0)") (class "Default")
      (node (ref "HR_REG") (pin "9") (pinfunction "S0_9") (pintype "input"))
      (node (ref "MUX2") (pin "12") (pinfunction "4Y_12") (pintype "output"))
    )
    (net (code "68") (name "Net-(HR_REG-S1)") (class "Default")
      (node (ref "HR_REG") (pin "10") (pinfunction "S1_10") (pintype "input"))
      (node (ref "MUX2") (pin "9") (pinfunction "3Y_9") (pintype "output"))
    )
    (net (code "69") (name "Net-(JKFF0-1J)") (class "Default")
      (node (ref "JKFF0") (pin "2") (pinfunction "1J_2") (pintype "input"))
      (node (ref "NAND1") (pin "10") (pinfunction "3B_10") (pintype "input"))
      (node (ref "NAND1") (pin "9") (pinfunction "3A_9") (pintype "input"))
      (node (ref "OR2") (pin "3") (pinfunction "1Y_3") (pintype "output"))
    )
    (net (code "70") (name "Net-(JKFF0-~{1K})") (class "Default")
      (node (ref "JKFF0") (pin "3") (pinfunction "~{1K}_3") (pintype "input"))
      (node (ref "NAND1") (pin "8") (pinfunction "3Y_8") (pintype "output"))
    )
    (net (code "71") (name "Net-(LO_MIN_MUX-X)") (class "Default")
      (node (ref "LO_MIN_MUX") (pin "13") (pinfunction "X_13") (pintype "bidirectional"))
      (node (ref "SPLI_REG") (pin "4") (pinfunction "B_4") (pintype "input"))
    )
    (net (code "72") (name "Net-(LO_MIN_MUX-X1)") (class "Default")
      (node (ref "LO_MIN_MUX") (pin "14") (pinfunction "X1_14") (pintype "bidirectional"))
      (node (ref "SPLIT_ADDER") (pin "13") (pinfunction "E3_13") (pintype "output"))
    )
    (net (code "73") (name "Net-(LO_MIN_MUX-Y)") (class "Default")
      (node (ref "LO_MIN_MUX") (pin "3") (pinfunction "Y_3") (pintype "bidirectional"))
      (node (ref "SPLI_REG") (pin "3") (pinfunction "A_3") (pintype "input"))
    )
    (net (code "74") (name "Net-(LO_MIN_MUX-Y1)") (class "Default")
      (node (ref "LO_MIN_MUX") (pin "5") (pinfunction "Y1_5") (pintype "bidirectional"))
      (node (ref "SPLIT_ADDER") (pin "10") (pinfunction "E4_10") (pintype "output"))
    )
    (net (code "75") (name "Net-(LO_SEC_ADDER-A1)") (class "Default")
      (node (ref "LO_SEC_ADDER") (pin "5") (pinfunction "A1_5") (pintype "input"))
      (node (ref "LO_SEC_REG") (pin "12") (pinfunction "QD_12") (pintype "output"))
      (node (ref "MS_REG") (pin "2") (pinfunction "SRSER_2") (pintype "input"))
    )
    (net (code "76") (name "Net-(LO_SEC_ADDER-A3)") (class "Default")
      (node (ref "LO_SEC_ADDER") (pin "11") (pinfunction "B4_11") (pintype "input"))
      (node (ref "LO_SEC_ADDER") (pin "14") (pinfunction "A3_14") (pintype "input"))
    )
    (net (code "77") (name "Net-(LO_SEC_ADDER-A4)") (class "Default")
      (node (ref "LO_SEC_ADDER") (pin "12") (pinfunction "A4_12") (pintype "input"))
      (node (ref "LO_SEC_REG") (pin "15") (pinfunction "QA_15") (pintype "output"))
      (node (ref "SPLI_REG") (pin "7") (pinfunction "SLSER_7") (pintype "input"))
    )
    (net (code "78") (name "Net-(LO_SEC_ADDER-B2)") (class "Default")
      (node (ref "LO_SEC_ADDER") (pin "2") (pinfunction "B2_2") (pintype "input"))
      (node (ref "LO_SEC_REG") (pin "13") (pinfunction "QC_13") (pintype "output"))
    )
    (net (code "79") (name "Net-(LO_SEC_ADDER-B3)") (class "Default")
      (node (ref "LO_SEC_ADDER") (pin "15") (pinfunction "B3_15") (pintype "input"))
      (node (ref "LO_SEC_REG") (pin "14") (pinfunction "QB_14") (pintype "output"))
    )
    (net (code "80") (name "Net-(LO_SEC_ADDER-E1)") (class "Default")
      (node (ref "LO_SEC_ADDER") (pin "4") (pinfunction "E1_4") (pintype "output"))
      (node (ref "LO_SEC_AND") (pin "13") (pinfunction "4B_13") (pintype "input"))
    )
    (net (code "81") (name "Net-(LO_SEC_ADDER-E2)") (class "Default")
      (node (ref "LO_SEC_ADDER") (pin "1") (pinfunction "E2_1") (pintype "output"))
      (node (ref "LO_SEC_AND") (pin "9") (pinfunction "3A_9") (pintype "input"))
    )
    (net (code "82") (name "Net-(LO_SEC_AND-1B)") (class "Default")
      (node (ref "LO_SEC_AND") (pin "10") (pinfunction "3B_10") (pintype "input"))
      (node (ref "LO_SEC_AND") (pin "12") (pinfunction "4A_12") (pintype "input"))
      (node (ref "LO_SEC_AND") (pin "2") (pinfunction "1B_2") (pintype "input"))
      (node (ref "LO_SEC_AND") (pin "4") (pinfunction "2A_4") (pintype "input"))
      (node (ref "NAND0") (pin "8") (pinfunction "3Y_8") (pintype "output"))
    )
    (net (code "83") (name "Net-(LO_SEC_AND-1Y)") (class "Default")
      (node (ref "LO_SEC_AND") (pin "3") (pinfunction "1Y_3") (pintype "output"))
      (node (ref "LO_SEC_REG") (pin "4") (pinfunction "B_4") (pintype "input"))
    )
    (net (code "84") (name "Net-(LO_SEC_AND-2Y)") (class "Default")
      (node (ref "LO_SEC_AND") (pin "6") (pinfunction "2Y_6") (pintype "output"))
      (node (ref "LO_SEC_REG") (pin "3") (pinfunction "A_3") (pintype "input"))
    )
    (net (code "85") (name "Net-(LO_SEC_AND-3Y)") (class "Default")
      (node (ref "LO_SEC_AND") (pin "8") (pinfunction "3Y_8") (pintype "output"))
      (node (ref "LO_SEC_REG") (pin "6") (pinfunction "D_6") (pintype "input"))
    )
    (net (code "86") (name "Net-(LO_SEC_AND-4Y)") (class "Default")
      (node (ref "LO_SEC_AND") (pin "11") (pinfunction "4Y_11") (pintype "output"))
      (node (ref "LO_SEC_REG") (pin "5") (pinfunction "C_5") (pintype "input"))
    )
    (net (code "87") (name "Net-(LO_SEC_REG-S0)") (class "Default")
      (node (ref "LO_SEC_REG") (pin "9") (pinfunction "S0_9") (pintype "input"))
      (node (ref "MUX1") (pin "7") (pinfunction "2Y_7") (pintype "output"))
    )
    (net (code "88") (name "Net-(LO_SEC_REG-S1)") (class "Default")
      (node (ref "LO_SEC_REG") (pin "10") (pinfunction "S1_10") (pintype "input"))
      (node (ref "MUX1") (pin "4") (pinfunction "1Y_4") (pintype "output"))
    )
    (net (code "89") (name "Net-(LO_SEC_REG-SLSER)") (class "Default")
      (node (ref "LO_SEC_REG") (pin "7") (pinfunction "SLSER_7") (pintype "input"))
      (node (ref "MS_ADDER") (pin "12") (pinfunction "A4_12") (pintype "input"))
      (node (ref "MS_REG") (pin "15") (pinfunction "QA_15") (pintype "output"))
    )
    (net (code "90") (name "Net-(MS_ADDER-A1)") (class "Default")
      (node (ref "MS_ADDER") (pin "5") (pinfunction "A1_5") (pintype "input"))
      (node (ref "MS_REG") (pin "12") (pinfunction "QD_12") (pintype "output"))
    )
    (net (code "91") (name "Net-(MS_ADDER-B2)") (class "Default")
      (node (ref "MS_ADDER") (pin "2") (pinfunction "B2_2") (pintype "input"))
      (node (ref "MS_REG") (pin "13") (pinfunction "QC_13") (pintype "output"))
    )
    (net (code "92") (name "Net-(MS_ADDER-B3)") (class "Default")
      (node (ref "MS_ADDER") (pin "15") (pinfunction "B3_15") (pintype "input"))
      (node (ref "MS_REG") (pin "14") (pinfunction "QB_14") (pintype "output"))
    )
    (net (code "93") (name "Net-(MS_ADDER-E1)") (class "Default")
      (node (ref "MS_ADDER") (pin "4") (pinfunction "E1_4") (pintype "output"))
      (node (ref "MS_AND") (pin "9") (pinfunction "3A_9") (pintype "input"))
      (node (ref "OR0") (pin "13") (pinfunction "4B_13") (pintype "input"))
    )
    (net (code "94") (name "Net-(MS_ADDER-E2)") (class "Default")
      (node (ref "MS_ADDER") (pin "1") (pinfunction "E2_1") (pintype "output"))
      (node (ref "MS_AND") (pin "13") (pinfunction "4B_13") (pintype "input"))
    )
    (net (code "95") (name "Net-(MS_ADDER-E3)") (class "Default")
      (node (ref "MS_ADDER") (pin "13") (pinfunction "E3_13") (pintype "output"))
      (node (ref "MS_AND") (pin "1") (pinfunction "1A_1") (pintype "input"))
      (node (ref "OR0") (pin "12") (pinfunction "4A_12") (pintype "input"))
    )
    (net (code "96") (name "Net-(MS_ADDER-E4)") (class "Default")
      (node (ref "MS_ADDER") (pin "10") (pinfunction "E4_10") (pintype "output"))
      (node (ref "MS_AND") (pin "5") (pinfunction "2B_5") (pintype "input"))
      (node (ref "NAND0") (pin "1") (pinfunction "1A_1") (pintype "input"))
    )
    (net (code "97") (name "Net-(MS_AND-1B)") (class "Default")
      (node (ref "MS_AND") (pin "10") (pinfunction "3B_10") (pintype "input"))
      (node (ref "MS_AND") (pin "12") (pinfunction "4A_12") (pintype "input"))
      (node (ref "MS_AND") (pin "2") (pinfunction "1B_2") (pintype "input"))
      (node (ref "MS_AND") (pin "4") (pinfunction "2A_4") (pintype "input"))
      (node (ref "NAND0") (pin "6") (pinfunction "2Y_6") (pintype "output"))
    )
    (net (code "98") (name "Net-(MS_AND-1Y)") (class "Default")
      (node (ref "MS_AND") (pin "3") (pinfunction "1Y_3") (pintype "output"))
      (node (ref "MS_REG") (pin "4") (pinfunction "B_4") (pintype "input"))
    )
    (net (code "99") (name "Net-(MS_AND-2Y)") (class "Default")
      (node (ref "MS_AND") (pin "6") (pinfunction "2Y_6") (pintype "output"))
      (node (ref "MS_REG") (pin "3") (pinfunction "A_3") (pintype "input"))
    )
    (net (code "100") (name "Net-(MS_AND-3Y)") (class "Default")
      (node (ref "MS_AND") (pin "8") (pinfunction "3Y_8") (pintype "output"))
      (node (ref "MS_REG") (pin "6") (pinfunction "D_6") (pintype "input"))
    )
    (net (code "101") (name "Net-(MS_AND-4Y)") (class "Default")
      (node (ref "MS_AND") (pin "11") (pinfunction "4Y_11") (pintype "output"))
      (node (ref "MS_REG") (pin "5") (pinfunction "C_5") (pintype "input"))
    )
    (net (code "102") (name "Net-(MUX1-1B)") (class "Default")
      (node (ref "MUX1") (pin "10") (pinfunction "3B_10") (pintype "input"))
      (node (ref "MUX1") (pin "3") (pinfunction "1B_3") (pintype "input"))
      (node (ref "OR0") (pin "3") (pinfunction "1Y_3") (pintype "output"))
    )
    (net (code "103") (name "Net-(MUX1-2B)") (class "Default")
      (node (ref "MUX1") (pin "13") (pinfunction "4B_13") (pintype "input"))
      (node (ref "MUX1") (pin "6") (pinfunction "2B_6") (pintype "input"))
      (node (ref "OR0") (pin "8") (pinfunction "3Y_8") (pintype "output"))
    )
    (net (code "104") (name "Net-(MUX1-3A)") (class "Default")
      (node (ref "MUX1") (pin "11") (pinfunction "3A_11") (pintype "input"))
      (node (ref "MUX1") (pin "14") (pinfunction "4A_14") (pintype "input"))
    )
    (net (code "105") (name "Net-(MUX1-3Y)") (class "Default")
      (node (ref "MUX1") (pin "9") (pinfunction "3Y_9") (pintype "output"))
      (node (ref "SPLI_REG") (pin "10") (pinfunction "S1_10") (pintype "input"))
    )
    (net (code "106") (name "Net-(MUX1-4Y)") (class "Default")
      (node (ref "MUX1") (pin "12") (pinfunction "4Y_12") (pintype "output"))
      (node (ref "SPLI_REG") (pin "9") (pinfunction "S0_9") (pintype "input"))
    )
    (net (code "107") (name "Net-(MUX2-1B)") (class "Default")
      (node (ref "MUX2") (pin "3") (pinfunction "1B_3") (pintype "input"))
      (node (ref "OR1") (pin "8") (pinfunction "3Y_8") (pintype "output"))
    )
    (net (code "108") (name "Net-(MUX2-2B)") (class "Default")
      (node (ref "MUX2") (pin "6") (pinfunction "2B_6") (pintype "input"))
      (node (ref "OR1") (pin "11") (pinfunction "4Y_11") (pintype "output"))
    )
    (net (code "109") (name "Net-(MUX2-3B)") (class "Default")
      (node (ref "MUX2") (pin "10") (pinfunction "3B_10") (pintype "input"))
      (node (ref "OR2") (pin "8") (pinfunction "3Y_8") (pintype "output"))
    )
    (net (code "110") (name "Net-(MUX2-4B)") (class "Default")
      (node (ref "MUX2") (pin "13") (pinfunction "4B_13") (pintype "input"))
      (node (ref "OR2") (pin "11") (pinfunction "4Y_11") (pintype "output"))
    )
    (net (code "111") (name "Net-(NAND0-1B)") (class "Default")
      (node (ref "NAND0") (pin "2") (pinfunction "1B_2") (pintype "input"))
      (node (ref "OR0") (pin "11") (pinfunction "4Y_11") (pintype "output"))
    )
    (net (code "112") (name "Net-(NAND0-1Y)") (class "Default")
      (node (ref "NAND0") (pin "12") (pinfunction "4A_12") (pintype "input"))
      (node (ref "NAND0") (pin "13") (pinfunction "4B_13") (pintype "input"))
      (node (ref "NAND0") (pin "3") (pinfunction "1Y_3") (pintype "output"))
      (node (ref "NAND0") (pin "4") (pinfunction "2A_4") (pintype "input"))
    )
    (net (code "113") (name "Net-(OR1-1B)") (class "Default")
      (node (ref "OR1") (pin "13") (pinfunction "4B_13") (pintype "input"))
      (node (ref "OR1") (pin "2") (pinfunction "1B_2") (pintype "input"))
      (node (ref "OR1") (pin "6") (pinfunction "2Y_6") (pintype "output"))
      (node (ref "OR1") (pin "9") (pinfunction "3A_9") (pintype "input"))
    )
    (net (code "114") (name "unconnected-(AND1-4A-Pad12)") (class "Default")
      (node (ref "AND1") (pin "12") (pinfunction "4A_12") (pintype "input"))
    )
    (net (code "115") (name "unconnected-(AND1-4B-Pad13)") (class "Default")
      (node (ref "AND1") (pin "13") (pinfunction "4B_13") (pintype "input"))
    )
    (net (code "116") (name "unconnected-(AND1-4Y-Pad11)") (class "Default")
      (node (ref "AND1") (pin "11") (pinfunction "4Y_11") (pintype "output"))
    )
    (net (code "117") (name "unconnected-(HI_MIN_ADDER-C4-Pad9)") (class "Default")
      (node (ref "HI_MIN_ADDER") (pin "9") (pinfunction "C4_9") (pintype "input"))
    )
    (net (code "118") (name "unconnected-(HR_ADDER-C4-Pad9)") (class "Default")
      (node (ref "HR_ADDER") (pin "9") (pinfunction "C4_9") (pintype "input"))
    )
    (net (code "119") (name "unconnected-(JKFF0-2CLK-Pad12)") (class "Default")
      (node (ref "JKFF0") (pin "12") (pinfunction "2CLK_12") (pintype "input"))
    )
    (net (code "120") (name "unconnected-(JKFF0-2J-Pad14)") (class "Default")
      (node (ref "JKFF0") (pin "14") (pinfunction "2J_14") (pintype "input"))
    )
    (net (code "121") (name "unconnected-(JKFF0-2Q-Pad10)") (class "Default")
      (node (ref "JKFF0") (pin "10") (pinfunction "2Q_10") (pintype "output"))
    )
    (net (code "122") (name "unconnected-(JKFF0-~{2CLR}-Pad15)") (class "Default")
      (node (ref "JKFF0") (pin "15") (pinfunction "~{2CLR}_15") (pintype "input"))
    )
    (net (code "123") (name "unconnected-(JKFF0-~{2K}-Pad13)") (class "Default")
      (node (ref "JKFF0") (pin "13") (pinfunction "~{2K}_13") (pintype "input"))
    )
    (net (code "124") (name "unconnected-(JKFF0-~{2PRE}-Pad11)") (class "Default")
      (node (ref "JKFF0") (pin "11") (pinfunction "~{2PRE}_11") (pintype "input"))
    )
    (net (code "125") (name "unconnected-(JKFF0-~{2Q}-Pad9)") (class "Default")
      (node (ref "JKFF0") (pin "9") (pinfunction "~{2Q}_9") (pintype "output"))
    )
    (net (code "126") (name "unconnected-(MS_ADDER-C4-Pad9)") (class "Default")
      (node (ref "MS_ADDER") (pin "9") (pinfunction "C4_9") (pintype "input"))
    )
    (net (code "127") (name "unconnected-(MUX1-~{G}-Pad15)") (class "Default")
      (node (ref "MUX1") (pin "15") (pinfunction "~{G}_15") (pintype "input"))
    )
    (net (code "128") (name "unconnected-(NAND1-4A-Pad12)") (class "Default")
      (node (ref "NAND1") (pin "12") (pinfunction "4A_12") (pintype "input"))
    )
    (net (code "129") (name "unconnected-(NAND1-4B-Pad13)") (class "Default")
      (node (ref "NAND1") (pin "13") (pinfunction "4B_13") (pintype "input"))
    )
    (net (code "130") (name "unconnected-(NAND1-4Y-Pad11)") (class "Default")
      (node (ref "NAND1") (pin "11") (pinfunction "4Y_11") (pintype "output"))
    )
    (net (code "131") (name "unconnected-(OR0-2A-Pad4)") (class "Default")
      (node (ref "OR0") (pin "4") (pinfunction "2A_4") (pintype "input"))
    )
    (net (code "132") (name "unconnected-(OR0-2B-Pad5)") (class "Default")
      (node (ref "OR0") (pin "5") (pinfunction "2B_5") (pintype "input"))
    )
    (net (code "133") (name "unconnected-(OR0-2Y-Pad6)") (class "Default")
      (node (ref "OR0") (pin "6") (pinfunction "2Y_6") (pintype "output"))
    )
    (net (code "134") (name "unconnected-(SPLI_REG-SRSER-Pad2)") (class "Default")
      (node (ref "SPLI_REG") (pin "2") (pinfunction "SRSER_2") (pintype "input"))
    )
  )
)
